# 04_Relays.net
KiCad netlist of a schematic drawn in Altium Designer
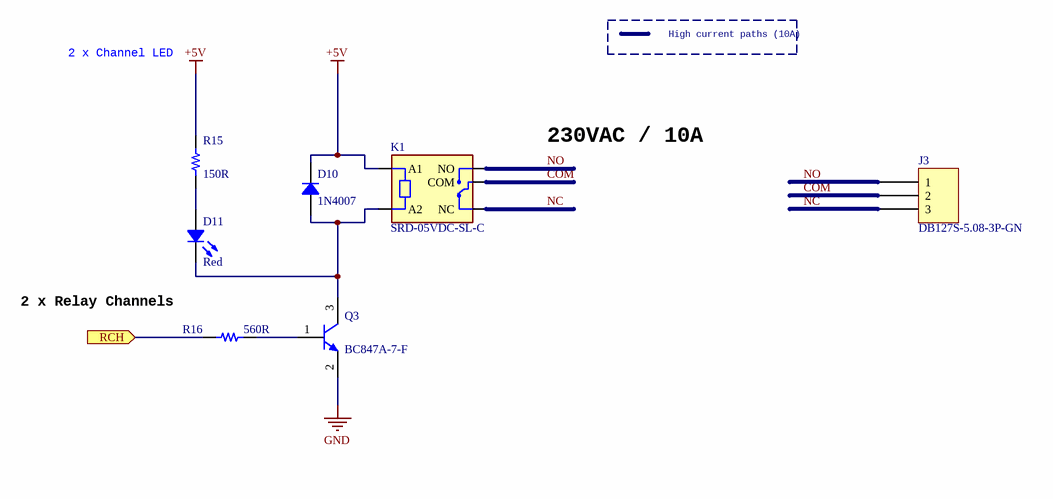
[diagram p0: 04.Relays.SchDoc]

(export (version "E")
  (design (tool "Eeschema 10.0.6"))
  (components
    (comp (ref "D10")
      (value "1N4007")
      (footprint "DO214AC SMA")
      (description "1A 1.1V@1A 1kV SMA(DO-214AC) Diodes - General Purpose ROHS")
      (fields (field (name "MANUFACTURER") "YONGYUTAI") (field (name "JLC PART NUMBER") "C2892673"))
      (libsource (lib "Celestial Altium Library - altium_library") (part "Diode"))
    )
    (comp (ref "D11")
      (value "Red")
      (footprint "LED 0603_1608 RED")
      (description "-40℃~+85℃ Red 0603 Light Emitting Diodes (LED) ROHS")
      (fields
        (field (name "MANUFACTURER PART NUMBER") "KT-0603R")
        (field (name "MANUFACTURER") "Hubei KENTO Elec")
      )
      (libsource (lib "Celestial Altium Library - altium_library") (part "LED"))
    )
    (comp (ref "J3")
      (value "DB127S-5.08-3P-GN")
      (footprint "TE 282837-3")
      (description "P=5.08mm Screw terminal ROHS")
      (fields (field (name "MANUFACTURER") "DIBO") (field (name "JLC PART NUMBER") "C2997520"))
      (libsource (lib "Celestial Altium Library - altium_library") (part "3 Pin"))
    )
    (comp (ref "K1")
      (value "SRD-05VDC-SL-C")
      (footprint "RELAY_SRD-05VDC-SL-C")
      (fields (field (name "MF") "Songle Relay"))
      (libsource (lib "Smart_Wifi_Control_System_Rev_A.1.0") (part "SRD-05VDC-SL-C"))
    )
    (comp (ref "Q3")
      (value "BC847A-7-F")
      (footprint "DIODES SOT-23-3")
      (description "65V 310mW 180@2mA,5V 100mA NPN SOT-23 Bipolar Transistors - BJT ROHS")
      (fields (field (name "MANUFACTURER") "Diodes Incorporated") (field (name "JLC PART NUMBER") "C2760576"))
      (libsource (lib "Celestial Altium Library - altium_library") (part "DIODES INC NPN SOT-23-3"))
    )
    (comp (ref "R15")
      (value "150R")
      (footprint "RES 0603_1608")
      (description "100mW Thick Film Resistors ±100ppm/℃ ±1% 150Ω 0603 Chip Resistor - Surface Mount ROHS")
      (fields
        (field (name "MANUFACTURER PART NUMBER") "RC0603FR-07150RL")
        (field (name "MANUFACTURER") "Yageo")
      )
      (libsource (lib "Celestial Altium Library - altium_library") (part "Resistor"))
    )
    (comp (ref "R16")
      (value "560R")
      (footprint "RES 0603_1608")
      (description "100mW ±100ppm/℃ ±1% 560Ω 0603 Chip Resistor - Surface Mount ROHS")
      (fields
        (field (name "MANUFACTURER PART NUMBER") "RS-03K5600FT")
        (field (name "MANUFACTURER") "FH (Guangdong Fenghua Advanced Tech)")
      )
      (libsource (lib "Celestial Altium Library - altium_library") (part "Resistor"))
    )
  )
  (nets
    (net (code "1") (name "+5V") (class "Default")
      (node (ref "D10") (pin "2") (pinfunction "2_2") (pintype "passive"))
      (node (ref "K1") (pin "A1") (pinfunction "A1_A1") (pintype "passive"))
      (node (ref "R15") (pin "2") (pinfunction "2_2") (pintype "passive"))
    )
    (net (code "2") (name "/COM") (class "Default")
      (node (ref "J3") (pin "2") (pinfunction "2_2") (pintype "passive"))
      (node (ref "K1") (pin "COM") (pinfunction "COM_COM") (pintype "passive"))
    )
    (net (code "3") (name "/NC") (class "Default")
      (node (ref "J3") (pin "3") (pinfunction "3_3") (pintype "passive"))
      (node (ref "K1") (pin "NC") (pinfunction "NC_NC") (pintype "passive"))
    )
    (net (code "4") (name "/NO") (class "Default")
      (node (ref "J3") (pin "1") (pinfunction "1_1") (pintype "passive"))
      (node (ref "K1") (pin "NO") (pinfunction "NO_NO") (pintype "passive"))
    )
    (net (code "5") (name "/RCH") (class "Default")
      (node (ref "R16") (pin "1") (pinfunction "1_1") (pintype "passive"))
    )
    (net (code "6") (name "GND") (class "Default")
      (node (ref "Q3") (pin "2") (pinfunction "E_2") (pintype "passive"))
    )
    (net (code "7") (name "Net-(D11-Pad1)") (class "Default")
      (node (ref "D11") (pin "1") (pinfunction "1_1") (pintype "passive"))
      (node (ref "R15") (pin "1") (pinfunction "1_1") (pintype "passive"))
    )
    (net (code "8") (name "Net-(Q3-B)") (class "Default")
      (node (ref "Q3") (pin "1") (pinfunction "B_1") (pintype "passive"))
      (node (ref "R16") (pin "2") (pinfunction "2_2") (pintype "passive"))
    )
    (net (code "9") (name "Net-(Q3-C)") (class "Default")
      (node (ref "D10") (pin "1") (pinfunction "1_1") (pintype "passive"))
      (node (ref "D11") (pin "2") (pinfunction "2_2") (pintype "passive"))
      (node (ref "K1") (pin "A2") (pinfunction "A2_A2") (pintype "passive"))
      (node (ref "Q3") (pin "3") (pinfunction "C_3") (pintype "passive"))
    )
  )
)
